# can-udp-bridge_0_1.net
KiCad netlist of a schematic drawn in EAGLE
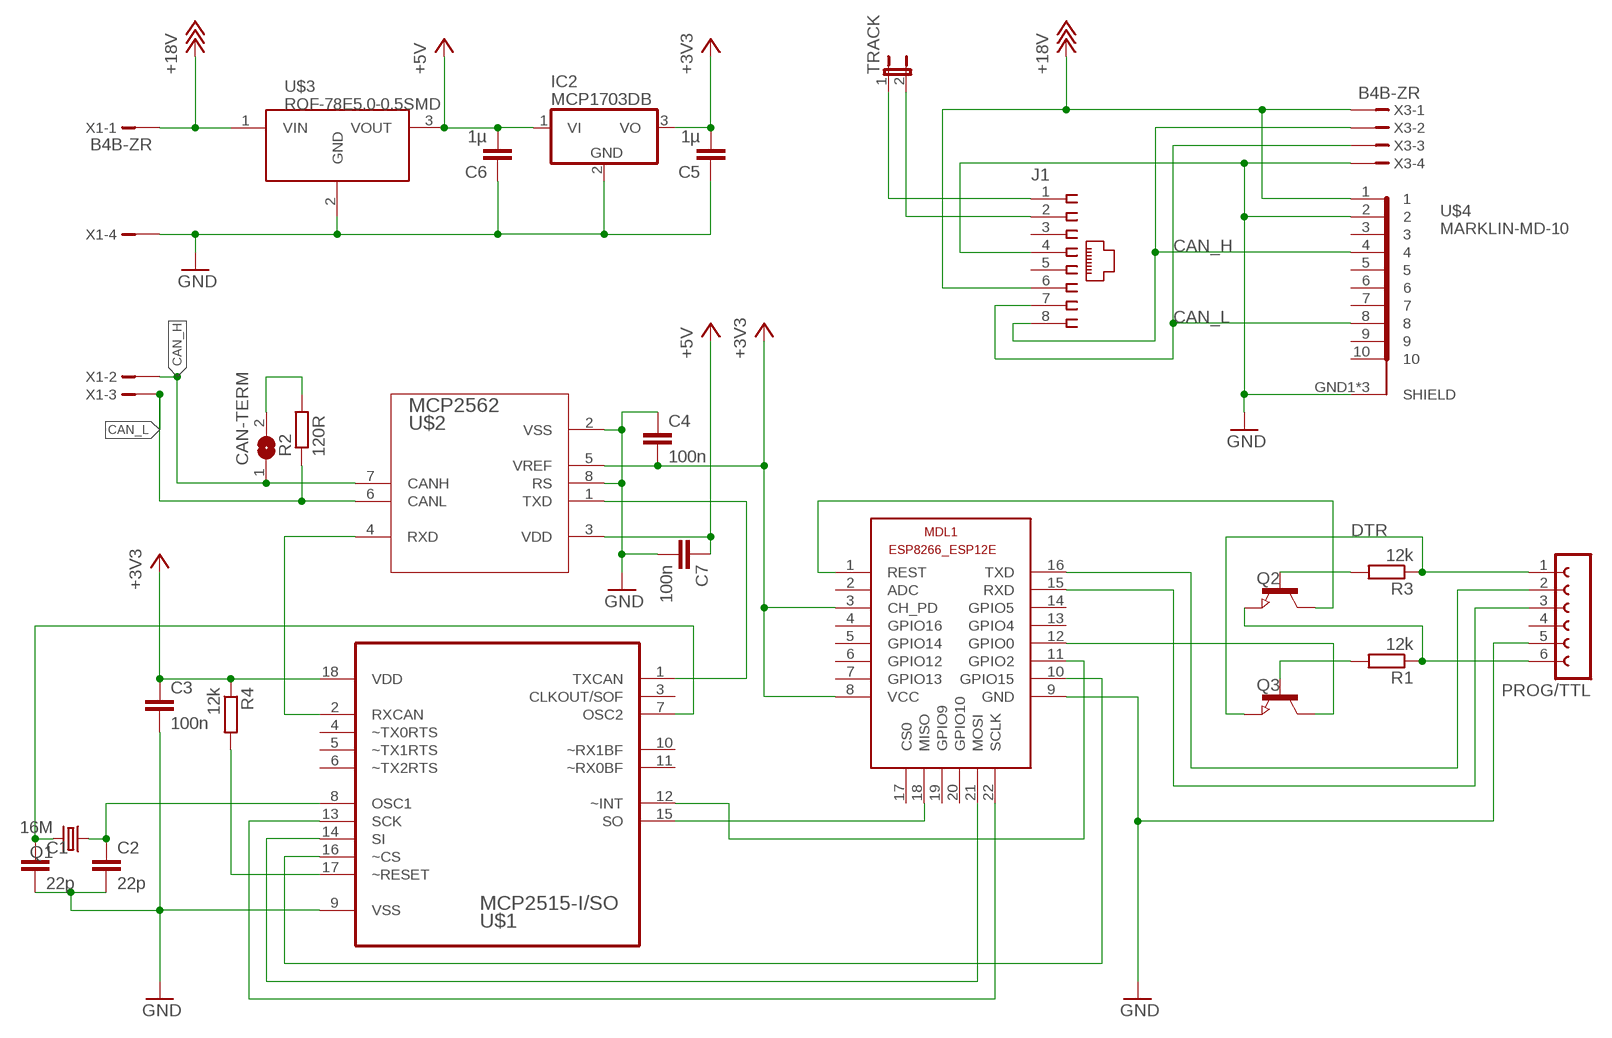
[diagram p0: schematic, sheet 1]

(export (version "E")
  (design (tool "Eeschema 10.0.6"))
  (components
    (comp (ref "C1")
      (value "22p")
      (footprint "eagle-import:C0805")
      (libsource (lib "eagle-import") (part "C-EUC0805"))
    )
    (comp (ref "C2")
      (value "22p")
      (footprint "eagle-import:C0805")
      (libsource (lib "eagle-import") (part "C-EUC0805"))
    )
    (comp (ref "C3")
      (value "100n")
      (footprint "eagle-import:C0805")
      (libsource (lib "eagle-import") (part "C-EUC0805"))
    )
    (comp (ref "C4")
      (value "100n")
      (footprint "eagle-import:C0805")
      (libsource (lib "eagle-import") (part "C-EUC0805"))
    )
    (comp (ref "C5")
      (value "1µ")
      (footprint "eagle-import:C0805")
      (libsource (lib "eagle-import") (part "C-EUC0805"))
    )
    (comp (ref "C6")
      (value "1µ")
      (footprint "eagle-import:C0805")
      (libsource (lib "eagle-import") (part "C-EUC0805"))
    )
    (comp (ref "C7")
      (value "100n")
      (footprint "eagle-import:C0805")
      (libsource (lib "eagle-import") (part "C-EUC0805"))
    )
    (comp (ref "CAN-TERM")
      (value "SJ")
      (footprint "eagle-import:SJ")
      (libsource (lib "eagle-import") (part "SJ"))
    )
    (comp (ref "IC2")
      (value "MCP1703DB")
      (footprint "eagle-import:SOT223")
      (libsource (lib "eagle-import") (part "MCP1703DB"))
    )
    (comp (ref "J1")
      (value "215877-7")
      (footprint "eagle-import:215877-7")
      (libsource (lib "eagle-import") (part "215877-7"))
    )
    (comp (ref "MDL1")
      (value "ESP8266-12EESP8266-ESP12E")
      (footprint "eagle-import:ESP8266-ESP12E")
      (libsource (lib "eagle-import") (part "ESP8266-12EESP8266-ESP12E"))
    )
    (comp (ref "PROG/TTL")
      (value "FE06W")
      (footprint "eagle-import:FE06W")
      (libsource (lib "eagle-import") (part "FE06W"))
    )
    (comp (ref "Q1")
      (value "16M")
      (footprint "eagle-import:CTS406")
      (libsource (lib "eagle-import") (part "CRYSTALCTS406"))
    )
    (comp (ref "Q2")
      (value "NPN-TRANSISTOR_SOT23")
      (footprint "eagle-import:SOT23")
      (libsource (lib "eagle-import") (part "NPN-TRANSISTOR_SOT23"))
    )
    (comp (ref "Q3")
      (value "NPN-TRANSISTOR_SOT23")
      (footprint "eagle-import:SOT23")
      (libsource (lib "eagle-import") (part "NPN-TRANSISTOR_SOT23"))
    )
    (comp (ref "R1")
      (value "12k")
      (footprint "eagle-import:R0805")
      (libsource (lib "eagle-import") (part "R-EU_R0805"))
    )
    (comp (ref "R2")
      (value "120R")
      (footprint "eagle-import:R0805")
      (libsource (lib "eagle-import") (part "R-EU_R0805"))
    )
    (comp (ref "R3")
      (value "12k")
      (footprint "eagle-import:R0805")
      (libsource (lib "eagle-import") (part "R-EU_R0805"))
    )
    (comp (ref "R4")
      (value "12k")
      (footprint "eagle-import:R0805")
      (libsource (lib "eagle-import") (part "R-EU_R0805"))
    )
    (comp (ref "TRACK")
      (value "JP1E")
      (footprint "eagle-import:JP1")
      (libsource (lib "eagle-import") (part "JP1E"))
    )
    (comp (ref "U$1")
      (value "MCP2515-I/SO")
      (footprint "eagle-import:SOIC127P1034X264-18N")
      (libsource (lib "eagle-import") (part "MCP2515-I/SO"))
    )
    (comp (ref "U$2")
      (value "MCP2562")
      (footprint "eagle-import:SOIC127P600X175-8N")
      (fields (field (name "MPN") "MCP2551-E/SN"))
      (libsource (lib "eagle-import") (part "MCP2551-E/SN"))
    )
    (comp (ref "U$3")
      (value "ROF-78E5.0-0.5SMD")
      (footprint "eagle-import:ROF-78EXX-0.5SMD")
      (libsource (lib "eagle-import") (part "ROF-78E5.0-0.5SMD"))
    )
    (comp (ref "U$4")
      (value "MARKLIN-MD-10")
      (footprint "eagle-import:MARKLIN-MD-10-PRINT")
      (libsource (lib "eagle-import") (part "MARKLIN-MD-10"))
    )
    (comp (ref "X1")
      (value "B4B-ZR")
      (footprint "eagle-import:B4B-ZR")
      (fields (field (name "MF") "FARNELL") (field (name "MPN") "B4B-ZR(LF)(SN)"))
      (libsource (lib "eagle-import") (part "?4B-ZRB"))
    )
    (comp (ref "X3")
      (value "B4B-ZR")
      (footprint "eagle-import:B4B-ZR")
      (fields (field (name "MF") "FARNELL") (field (name "MPN") "B4B-ZR(LF)(SN)"))
      (libsource (lib "eagle-import") (part "?4B-ZRB"))
    )
  )
  (nets
    (net (code "1") (name "+3V3") (class "Default")
      (node (ref "C3") (pin "1") (pinfunction "1_1") (pintype "passive"))
      (node (ref "C4") (pin "2") (pinfunction "2_2") (pintype "passive"))
      (node (ref "C5") (pin "2") (pinfunction "2_2") (pintype "passive"))
      (node (ref "IC2") (pin "3") (pinfunction "VO_3") (pintype "passive"))
      (node (ref "MDL1") (pin "3") (pinfunction "CH_PD_3") (pintype "bidirectional"))
      (node (ref "MDL1") (pin "8") (pinfunction "VCC_8") (pintype "bidirectional"))
      (node (ref "R4") (pin "1") (pinfunction "1_1") (pintype "passive"))
      (node (ref "U$1") (pin "18") (pinfunction "VDD_18") (pintype "power_in"))
      (node (ref "U$2") (pin "5") (pinfunction "VREF_5") (pintype "input"))
    )
    (net (code "2") (name "+5V") (class "Default")
      (node (ref "C6") (pin "2") (pinfunction "2_2") (pintype "passive"))
      (node (ref "C7") (pin "1") (pinfunction "1_1") (pintype "passive"))
      (node (ref "IC2") (pin "1") (pinfunction "VI_1") (pintype "input"))
      (node (ref "U$2") (pin "3") (pinfunction "VDD_3") (pintype "power_in"))
      (node (ref "U$3") (pin "3") (pinfunction "VOUT_3") (pintype "bidirectional"))
    )
    (net (code "3") (name "+18V") (class "Default")
      (node (ref "J1") (pin "6") (pinfunction "6_6") (pintype "passive"))
      (node (ref "U$3") (pin "1") (pinfunction "VIN_1") (pintype "bidirectional"))
      (node (ref "U$4") (pin "1") (pinfunction "1_1") (pintype "bidirectional"))
      (node (ref "X1") (pin "1") (pinfunction "1_1") (pintype "passive"))
      (node (ref "X3") (pin "1") (pinfunction "1_1") (pintype "passive"))
    )
    (net (code "4") (name "/DTR") (class "Default")
      (node (ref "PROG/TTL") (pin "1") (pinfunction "1_1") (pintype "passive"))
      (node (ref "Q3") (pin "2") (pinfunction "E_2") (pintype "passive"))
      (node (ref "R3") (pin "1") (pinfunction "1_1") (pintype "passive"))
    )
    (net (code "5") (name "CAN_H") (class "Default")
      (node (ref "CAN-TERM") (pin "1") (pinfunction "1_1") (pintype "passive"))
      (node (ref "J1") (pin "8") (pinfunction "8_8") (pintype "passive"))
      (node (ref "U$2") (pin "7") (pinfunction "CANH_7") (pintype "output"))
      (node (ref "U$4") (pin "4") (pinfunction "4_4") (pintype "bidirectional"))
      (node (ref "X1") (pin "2") (pinfunction "1_2") (pintype "passive"))
      (node (ref "X3") (pin "2") (pinfunction "1_2") (pintype "passive"))
    )
    (net (code "6") (name "CAN_L") (class "Default")
      (node (ref "J1") (pin "7") (pinfunction "7_7") (pintype "passive"))
      (node (ref "R2") (pin "1") (pinfunction "1_1") (pintype "passive"))
      (node (ref "U$2") (pin "6") (pinfunction "CANL_6") (pintype "output"))
      (node (ref "U$4") (pin "8") (pinfunction "8_8") (pintype "bidirectional"))
      (node (ref "X1") (pin "3") (pinfunction "1_3") (pintype "passive"))
      (node (ref "X3") (pin "3") (pinfunction "1_3") (pintype "passive"))
    )
    (net (code "7") (name "GND") (class "Default")
      (node (ref "C1") (pin "2") (pinfunction "2_2") (pintype "passive"))
      (node (ref "C2") (pin "2") (pinfunction "2_2") (pintype "passive"))
      (node (ref "C3") (pin "2") (pinfunction "2_2") (pintype "passive"))
      (node (ref "C4") (pin "1") (pinfunction "1_1") (pintype "passive"))
      (node (ref "C5") (pin "1") (pinfunction "1_1") (pintype "passive"))
      (node (ref "C6") (pin "1") (pinfunction "1_1") (pintype "passive"))
      (node (ref "C7") (pin "2") (pinfunction "2_2") (pintype "passive"))
      (node (ref "IC2") (pin "2") (pinfunction "GND_2") (pintype "passive"))
      (node (ref "J1") (pin "4") (pinfunction "4_4") (pintype "passive"))
      (node (ref "MDL1") (pin "9") (pinfunction "GND_9") (pintype "bidirectional"))
      (node (ref "PROG/TTL") (pin "5") (pinfunction "5_5") (pintype "passive"))
      (node (ref "U$1") (pin "9") (pinfunction "VSS_9") (pintype "power_in"))
      (node (ref "U$2") (pin "2") (pinfunction "VSS_2") (pintype "power_in"))
      (node (ref "U$2") (pin "8") (pinfunction "RS_8") (pintype "input"))
      (node (ref "U$3") (pin "2") (pinfunction "GND_2") (pintype "bidirectional"))
      (node (ref "U$4") (pin "2") (pinfunction "2_2") (pintype "bidirectional"))
      (node (ref "U$4") (pin "GND1") (pinfunction "SHIELD_GND1") (pintype "bidirectional"))
      (node (ref "U$4") (pin "GND2") (pinfunction "SHIELD_GND2") (pintype "bidirectional"))
      (node (ref "U$4") (pin "GND3") (pinfunction "SHIELD_GND3") (pintype "bidirectional"))
      (node (ref "X1") (pin "4") (pinfunction "1_4") (pintype "passive"))
      (node (ref "X3") (pin "4") (pinfunction "1_4") (pintype "passive"))
    )
    (net (code "8") (name "Net-(CAN-TERM-Pad2)") (class "Default")
      (node (ref "CAN-TERM") (pin "2") (pinfunction "2_2") (pintype "passive"))
      (node (ref "R2") (pin "2") (pinfunction "2_2") (pintype "passive"))
    )
    (net (code "9") (name "Net-(J1-Pad1)") (class "Default")
      (node (ref "J1") (pin "1") (pinfunction "1_1") (pintype "passive"))
      (node (ref "TRACK") (pin "1") (pinfunction "1_1") (pintype "passive"))
    )
    (net (code "10") (name "Net-(J1-Pad2)") (class "Default")
      (node (ref "J1") (pin "2") (pinfunction "2_2") (pintype "passive"))
      (node (ref "TRACK") (pin "2") (pinfunction "2_2") (pintype "passive"))
    )
    (net (code "11") (name "Net-(MDL1-GPIO0)") (class "Default")
      (node (ref "MDL1") (pin "12") (pinfunction "GPIO0_12") (pintype "bidirectional"))
      (node (ref "Q3") (pin "3") (pinfunction "C_3") (pintype "passive"))
    )
    (net (code "12") (name "Net-(MDL1-GPIO2)") (class "Default")
      (node (ref "MDL1") (pin "11") (pinfunction "GPIO2_11") (pintype "bidirectional"))
      (node (ref "U$1") (pin "12") (pinfunction "~{INT}_12") (pintype "output"))
    )
    (net (code "13") (name "Net-(MDL1-GPIO15)") (class "Default")
      (node (ref "MDL1") (pin "10") (pinfunction "GPIO15_10") (pintype "bidirectional"))
      (node (ref "U$1") (pin "16") (pinfunction "~{CS}_16") (pintype "input"))
    )
    (net (code "14") (name "Net-(MDL1-MISO)") (class "Default")
      (node (ref "MDL1") (pin "18") (pinfunction "MISO_18") (pintype "bidirectional"))
      (node (ref "U$1") (pin "15") (pinfunction "SO_15") (pintype "output"))
    )
    (net (code "15") (name "Net-(MDL1-MOSI)") (class "Default")
      (node (ref "MDL1") (pin "21") (pinfunction "MOSI_21") (pintype "bidirectional"))
      (node (ref "U$1") (pin "14") (pinfunction "SI_14") (pintype "input"))
    )
    (net (code "16") (name "Net-(MDL1-REST)") (class "Default")
      (node (ref "MDL1") (pin "1") (pinfunction "REST_1") (pintype "bidirectional"))
      (node (ref "Q2") (pin "3") (pinfunction "C_3") (pintype "passive"))
    )
    (net (code "17") (name "Net-(MDL1-RXD)") (class "Default")
      (node (ref "MDL1") (pin "15") (pinfunction "RXD_15") (pintype "bidirectional"))
      (node (ref "PROG/TTL") (pin "3") (pinfunction "3_3") (pintype "passive"))
    )
    (net (code "18") (name "Net-(MDL1-SCLK)") (class "Default")
      (node (ref "MDL1") (pin "22") (pinfunction "SCLK_22") (pintype "bidirectional"))
      (node (ref "U$1") (pin "13") (pinfunction "SCK_13") (pintype "input"))
    )
    (net (code "19") (name "Net-(MDL1-TXD)") (class "Default")
      (node (ref "MDL1") (pin "16") (pinfunction "TXD_16") (pintype "bidirectional"))
      (node (ref "PROG/TTL") (pin "2") (pinfunction "2_2") (pintype "passive"))
    )
    (net (code "20") (name "Net-(Q1-2)") (class "Default")
      (node (ref "C1") (pin "1") (pinfunction "1_1") (pintype "passive"))
      (node (ref "Q1") (pin "3") (pinfunction "2_3") (pintype "passive"))
      (node (ref "U$1") (pin "7") (pinfunction "OSC2_7") (pintype "output"))
    )
    (net (code "21") (name "Net-(Q2-B)") (class "Default")
      (node (ref "Q2") (pin "1") (pinfunction "B_1") (pintype "passive"))
      (node (ref "R3") (pin "2") (pinfunction "2_2") (pintype "passive"))
    )
    (net (code "22") (name "Net-(Q2-E)") (class "Default")
      (node (ref "PROG/TTL") (pin "6") (pinfunction "6_6") (pintype "passive"))
      (node (ref "Q2") (pin "2") (pinfunction "E_2") (pintype "passive"))
      (node (ref "R1") (pin "1") (pinfunction "1_1") (pintype "passive"))
    )
    (net (code "23") (name "Net-(Q3-B)") (class "Default")
      (node (ref "Q3") (pin "1") (pinfunction "B_1") (pintype "passive"))
      (node (ref "R1") (pin "2") (pinfunction "2_2") (pintype "passive"))
    )
    (net (code "24") (name "Net-(U$1-OSC1)") (class "Default")
      (node (ref "C2") (pin "1") (pinfunction "1_1") (pintype "passive"))
      (node (ref "Q1") (pin "1") (pinfunction "1_1") (pintype "passive"))
      (node (ref "U$1") (pin "8") (pinfunction "OSC1_8") (pintype "input"))
    )
    (net (code "25") (name "Net-(U$1-RXCAN)") (class "Default")
      (node (ref "U$1") (pin "2") (pinfunction "RXCAN_2") (pintype "input"))
      (node (ref "U$2") (pin "4") (pinfunction "RXD_4") (pintype "output"))
    )
    (net (code "26") (name "Net-(U$1-TXCAN)") (class "Default")
      (node (ref "U$1") (pin "1") (pinfunction "TXCAN_1") (pintype "output"))
      (node (ref "U$2") (pin "1") (pinfunction "TXD_1") (pintype "input"))
    )
    (net (code "27") (name "Net-(U$1-~{RESET})") (class "Default")
      (node (ref "R4") (pin "2") (pinfunction "2_2") (pintype "passive"))
      (node (ref "U$1") (pin "17") (pinfunction "~{RESET}_17") (pintype "input"))
    )
    (net (code "28") (name "unconnected-(J1-Pad3)") (class "Default")
      (node (ref "J1") (pin "3") (pinfunction "3_3") (pintype "passive"))
    )
    (net (code "29") (name "unconnected-(J1-Pad5)") (class "Default")
      (node (ref "J1") (pin "5") (pinfunction "5_5") (pintype "passive"))
    )
    (net (code "30") (name "unconnected-(MDL1-ADC-Pad2)") (class "Default")
      (node (ref "MDL1") (pin "2") (pinfunction "ADC_2") (pintype "bidirectional"))
    )
    (net (code "31") (name "unconnected-(MDL1-CS0-Pad17)") (class "Default")
      (node (ref "MDL1") (pin "17") (pinfunction "CS0_17") (pintype "bidirectional"))
    )
    (net (code "32") (name "unconnected-(MDL1-GPIO4-Pad13)") (class "Default")
      (node (ref "MDL1") (pin "13") (pinfunction "GPIO4_13") (pintype "bidirectional"))
    )
    (net (code "33") (name "unconnected-(MDL1-GPIO5-Pad14)") (class "Default")
      (node (ref "MDL1") (pin "14") (pinfunction "GPIO5_14") (pintype "bidirectional"))
    )
    (net (code "34") (name "unconnected-(MDL1-GPIO9-Pad19)") (class "Default")
      (node (ref "MDL1") (pin "19") (pinfunction "GPIO9_19") (pintype "bidirectional"))
    )
    (net (code "35") (name "unconnected-(MDL1-GPIO10-Pad20)") (class "Default")
      (node (ref "MDL1") (pin "20") (pinfunction "GPIO10_20") (pintype "bidirectional"))
    )
    (net (code "36") (name "unconnected-(MDL1-GPIO12-Pad6)") (class "Default")
      (node (ref "MDL1") (pin "6") (pinfunction "GPIO12_6") (pintype "bidirectional"))
    )
    (net (code "37") (name "unconnected-(MDL1-GPIO13-Pad7)") (class "Default")
      (node (ref "MDL1") (pin "7") (pinfunction "GPIO13_7") (pintype "bidirectional"))
    )
    (net (code "38") (name "unconnected-(MDL1-GPIO14-Pad5)") (class "Default")
      (node (ref "MDL1") (pin "5") (pinfunction "GPIO14_5") (pintype "bidirectional"))
    )
    (net (code "39") (name "unconnected-(MDL1-GPIO16-Pad4)") (class "Default")
      (node (ref "MDL1") (pin "4") (pinfunction "GPIO16_4") (pintype "bidirectional"))
    )
    (net (code "40") (name "unconnected-(PROG/TTL-Pad4)") (class "Default")
      (node (ref "PROG/TTL") (pin "4") (pinfunction "4_4") (pintype "passive"))
    )
    (net (code "41") (name "unconnected-(U$1-CLKOUT{slash}SOF-Pad3)") (class "Default")
      (node (ref "U$1") (pin "3") (pinfunction "CLKOUT/SOF_3") (pintype "output"))
    )
    (net (code "42") (name "unconnected-(U$1-~{RX0BF}-Pad11)") (class "Default")
      (node (ref "U$1") (pin "11") (pinfunction "~{RX0BF}_11") (pintype "output"))
    )
    (net (code "43") (name "unconnected-(U$1-~{RX1BF}-Pad10)") (class "Default")
      (node (ref "U$1") (pin "10") (pinfunction "~{RX1BF}_10") (pintype "output"))
    )
    (net (code "44") (name "unconnected-(U$1-~{TX0RTS}-Pad4)") (class "Default")
      (node (ref "U$1") (pin "4") (pinfunction "~{TX0RTS}_4") (pintype "input"))
    )
    (net (code "45") (name "unconnected-(U$1-~{TX1RTS}-Pad5)") (class "Default")
      (node (ref "U$1") (pin "5") (pinfunction "~{TX1RTS}_5") (pintype "input"))
    )
    (net (code "46") (name "unconnected-(U$1-~{TX2RTS}-Pad6)") (class "Default")
      (node (ref "U$1") (pin "6") (pinfunction "~{TX2RTS}_6") (pintype "input"))
    )
    (net (code "47") (name "unconnected-(U$4-Pad3)") (class "Default")
      (node (ref "U$4") (pin "3") (pinfunction "3_3") (pintype "bidirectional"))
    )
    (net (code "48") (name "unconnected-(U$4-Pad5)") (class "Default")
      (node (ref "U$4") (pin "5") (pinfunction "5_5") (pintype "bidirectional"))
    )
    (net (code "49") (name "unconnected-(U$4-Pad6)") (class "Default")
      (node (ref "U$4") (pin "6") (pinfunction "6_6") (pintype "bidirectional"))
    )
    (net (code "50") (name "unconnected-(U$4-Pad7)") (class "Default")
      (node (ref "U$4") (pin "7") (pinfunction "7_7") (pintype "bidirectional"))
    )
    (net (code "51") (name "unconnected-(U$4-Pad9)") (class "Default")
      (node (ref "U$4") (pin "9") (pinfunction "9_9") (pintype "bidirectional"))
    )
    (net (code "52") (name "unconnected-(U$4-Pad10)") (class "Default")
      (node (ref "U$4") (pin "10") (pinfunction "10_10") (pintype "bidirectional"))
    )
  )
)
